# Power.net
KiCad netlist of a schematic drawn in Altium Designer
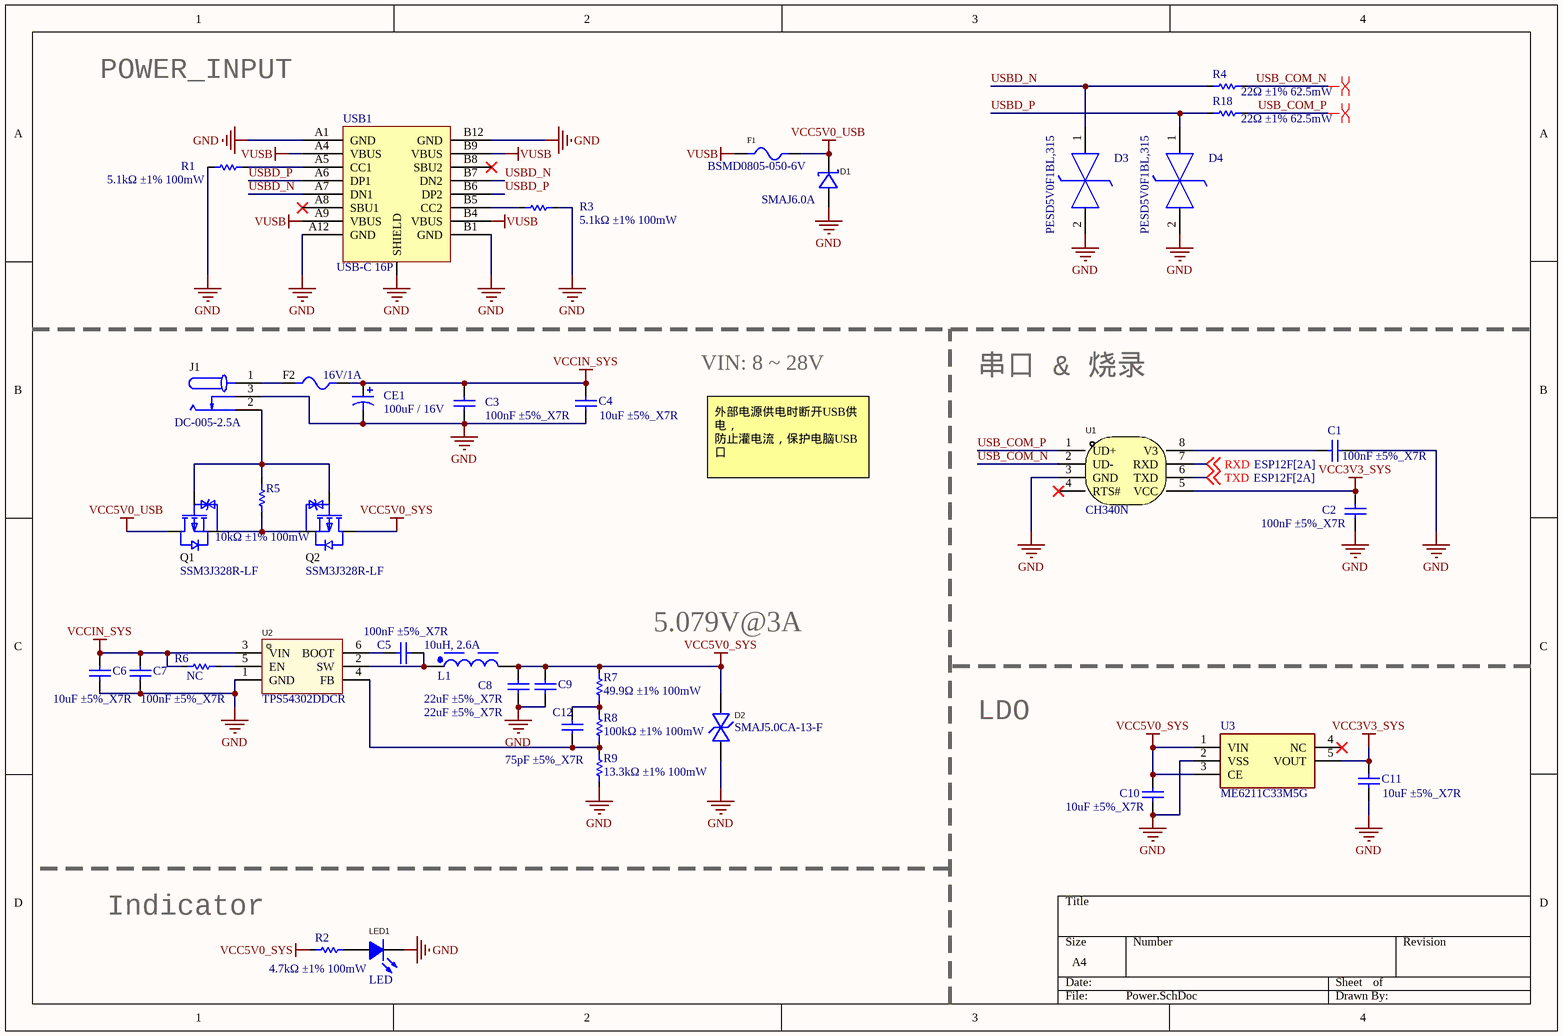
[diagram p0: Power.SchDoc]

(export (version "E")
  (design (tool "Eeschema 10.0.6"))
  (components
    (comp (ref "C1")
      (value "100nF ±5%_X7R")
      (footprint "C0603")
      (description "Capacitor")
      (fields (field (name "PUBLISHER") "Altium Limited"))
      (libsource (lib "Component") (part "Cap"))
    )
    (comp (ref "C2")
      (value "100nF ±5%_X7R")
      (footprint "C0603")
      (description "Capacitor")
      (fields (field (name "PUBLISHER") "Altium Limited"))
      (libsource (lib "Component") (part "Cap"))
    )
    (comp (ref "C3")
      (value "100nF ±5%_X7R")
      (footprint "C0603")
      (description "Capacitor")
      (fields (field (name "PUBLISHER") "Altium Limited"))
      (libsource (lib "Component") (part "Cap"))
    )
    (comp (ref "C4")
      (value "10uF ±5%_X7R")
      (footprint "C0603")
      (description "Capacitor")
      (fields (field (name "PUBLISHER") "Altium Limited"))
      (libsource (lib "Component") (part "Cap"))
    )
    (comp (ref "C5")
      (value "100nF ±5%_X7R")
      (footprint "C0402")
      (description "Capacitor")
      (fields (field (name "PUBLISHER") "Altium Limited"))
      (libsource (lib "Component") (part "Cap"))
    )
    (comp (ref "C6")
      (value "10uF ±5%_X7R")
      (footprint "C0603")
      (description "Capacitor")
      (fields (field (name "PUBLISHER") "Altium Limited"))
      (libsource (lib "Component") (part "Cap"))
    )
    (comp (ref "C7")
      (value "100nF ±5%_X7R")
      (footprint "C0603")
      (description "Capacitor")
      (fields (field (name "PUBLISHER") "Altium Limited"))
      (libsource (lib "Component") (part "Cap"))
    )
    (comp (ref "C8")
      (value "22uF ±5%_X7R")
      (footprint "C0603")
      (description "Capacitor")
      (fields (field (name "PUBLISHER") "Altium Limited"))
      (libsource (lib "Component") (part "Cap"))
    )
    (comp (ref "C9")
      (value "22uF ±5%_X7R")
      (footprint "C0603")
      (description "Capacitor")
      (fields (field (name "PUBLISHER") "Altium Limited"))
      (libsource (lib "Component") (part "Cap"))
    )
    (comp (ref "C10")
      (value "10uF ±5%_X7R")
      (footprint "C0603")
      (description "Capacitor")
      (fields (field (name "PUBLISHER") "Altium Limited"))
      (libsource (lib "Component") (part "Cap"))
    )
    (comp (ref "C11")
      (value "10uF ±5%_X7R")
      (footprint "C0603")
      (description "Capacitor")
      (fields (field (name "PUBLISHER") "Altium Limited"))
      (libsource (lib "Component") (part "Cap"))
    )
    (comp (ref "C12")
      (value "75pF ±5%_X7R")
      (footprint "C0402")
      (description "Capacitor")
      (fields (field (name "PUBLISHER") "Altium Limited"))
      (libsource (lib "Component") (part "Cap"))
    )
    (comp (ref "CE1")
      (value "100uF / 16V")
      (footprint "CAP-SMD")
      (description "Polarized Capacitor (Axial)")
      (fields (field (name "PUBLISHER") "Altium Limited"))
      (libsource (lib "Component") (part "Cap Pol"))
    )
    (comp (ref "D1")
      (value "SMAJ6.0A")
      (footprint "SMA_L4.4-W2.6-LS5.0-RD")
      (fields (field (name "MANUFACTURER") "BORN(伯恩半导体)"))
      (libsource (lib "Component") (part "SMAJ6.0A_C152112"))
    )
    (comp (ref "D2")
      (value "SMAJ5.0CA-13-F")
      (footprint "SMA_L4.4-W2.6-LS5.0-BI")
      (fields (field (name "MANUFACTURER") "DIODES(美台)"))
      (libsource (lib "Component") (part "SMAJ5.0CA"))
    )
    (comp (ref "D3")
      (value "PESD5V0F1BL,315")
      (footprint "SamacSys:PESD5V0S1BL315")
      (description "Diode ESD (Bi-directional)")
      (fields (field (name "MOUSER PART NUMBER") "771-PESD5V0F1BL315"))
      (libsource (lib "*") (part "PESD5V0F1BL,315"))
    )
    (comp (ref "D4")
      (value "PESD5V0F1BL,315")
      (footprint "SamacSys:PESD5V0S1BL315")
      (description "Diode ESD (Bi-directional)")
      (fields (field (name "MOUSER PART NUMBER") "771-PESD5V0F1BL315"))
      (libsource (lib "*") (part "PESD5V0F1BL,315"))
    )
    (comp (ref "F1")
      (value "BSMD0805-050-6V")
      (footprint "F0805")
      (fields (field (name "MANUFACTURER") "BHFUSE(佰宏)"))
      (libsource (lib "Component_Footprints") (part "BSMD0805-050-6V"))
    )
    (comp (ref "F2")
      (value "16V/1A")
      (footprint "F1206")
      (fields (field (name "MANUFACTURER") "BHFUSE(佰宏)") (field (name "MANUFACTURER PART") "BSMD0805-050-6V"))
      (libsource (lib "Component") (part "FUSE"))
    )
    (comp (ref "J1")
      (value "DC-005-2.5A")
      (footprint "CONN-TH_DC-005-2.5A-2.0")
      (fields
        (field (name "MANUFACTURER") "XKB Connectivity(中国星坤)")
        (field (name "MANUFACTURER PART") "DC-005-2.5A-2.5")
      )
      (libsource (lib "Connectivity_Plugs") (part "DC-005"))
    )
    (comp (ref "L1")
      (value "10uH, 2.6A")
      (footprint "WE-PD_7345P")
      (description "WE-PD SMT Power Inductor, size 7345P, 10uH, 2.6A, 45mOhm")
      (fields
        (field (name "MANUFACTURER PART NUMBER") "7447773100")
        (field (name "MANUFACTURER") "Wurth Elektronik")
      )
      (libsource (lib "WE-PD (rev22g)") (part "7447773100"))
    )
    (comp (ref "LED1")
      (value "LED")
      (footprint "LED0603-RD")
      (fields
        (field (name "MANUFACTURER") "EVERLIGHT(亿光)")
        (field (name "MANUFACTURER PART") "17-21SURC/S530-A2/TR8")
      )
      (libsource (lib "Component") (part "LED"))
    )
    (comp (ref "Q1")
      (value "SSM3J328R-LF")
      (footprint "SOT-23-3_L2.9-W1.4-P1.91-LS2.6-BR")
      (fields (field (name "MANUFACTURER") "VBsemi(微碧)") (field (name "MANUFACTURER PART") "SSM3J328R-VB"))
      (libsource (lib "Component") (part "MOSFET"))
    )
    (comp (ref "Q2")
      (value "SSM3J328R-LF")
      (footprint "SOT-23-3_L2.9-W1.4-P1.91-LS2.6-BR")
      (fields (field (name "MANUFACTURER") "VBsemi(微碧)") (field (name "MANUFACTURER PART") "SSM3J328R-VB"))
      (libsource (lib "Component") (part "MOSFET"))
    )
    (comp (ref "R1")
      (value "5.1kΩ ±1% 100mW")
      (footprint "R0402")
      (description "Resistor")
      (fields (field (name "PUBLISHER") "Altium Limited"))
      (libsource (lib "Component_Footprints") (part "Res"))
    )
    (comp (ref "R2")
      (value "4.7kΩ ±1% 100mW")
      (footprint "R0603")
      (description "Resistor")
      (fields (field (name "PUBLISHER") "Altium Limited"))
      (libsource (lib "Component_Footprints") (part "Res"))
    )
    (comp (ref "R3")
      (value "5.1kΩ ±1% 100mW")
      (footprint "R0402")
      (description "Resistor")
      (fields (field (name "PUBLISHER") "Altium Limited"))
      (libsource (lib "Component_Footprints") (part "Res"))
    )
    (comp (ref "R4")
      (value "22Ω ±1% 62.5mW")
      (footprint "R0402")
      (description "Resistor")
      (fields (field (name "PUBLISHER") "Altium Limited"))
      (libsource (lib "Component") (part "Res"))
    )
    (comp (ref "R5")
      (value "10kΩ ±1% 100mW")
      (footprint "R0603")
      (description "Resistor")
      (fields (field (name "PUBLISHER") "Altium Limited"))
      (libsource (lib "Component") (part "Res"))
    )
    (comp (ref "R6")
      (value "NC")
      (footprint "R0402")
      (description "Resistor")
      (fields (field (name "PUBLISHER") "Altium Limited"))
      (libsource (lib "Component") (part "Res"))
    )
    (comp (ref "R7")
      (value "49.9Ω ±1% 100mW")
      (footprint "R0402")
      (description "Resistor")
      (fields (field (name "PUBLISHER") "Altium Limited"))
      (libsource (lib "Component") (part "Res"))
    )
    (comp (ref "R8")
      (value "100kΩ ±1% 100mW")
      (footprint "R0402")
      (description "Resistor")
      (fields (field (name "PUBLISHER") "Altium Limited"))
      (libsource (lib "Component") (part "Res"))
    )
    (comp (ref "R9")
      (value "13.3kΩ ±1% 100mW")
      (footprint "R0402")
      (description "Resistor")
      (fields (field (name "PUBLISHER") "Altium Limited"))
      (libsource (lib "Component") (part "Res"))
    )
    (comp (ref "R18")
      (value "22Ω ±1% 62.5mW")
      (footprint "R0402")
      (description "Resistor")
      (fields (field (name "PUBLISHER") "Altium Limited"))
      (libsource (lib "Component") (part "Res"))
    )
    (comp (ref "U1")
      (value "CH340N")
      (footprint "SOP-8_L4.9-W3.9-P1.27-LS6.0-BL")
      (fields (field (name "MANUFACTURER") "WCH(南京沁恒)"))
      (libsource (lib "IC") (part "CH340N"))
    )
    (comp (ref "U2")
      (value "TPS54302DDCR")
      (footprint "SOT-23-6_L2.9-W1.6-P0.95-LS2.8-BL")
      (fields (field (name "MANUFACTURER") "TI(德州仪器)"))
      (libsource (lib "IC") (part "TPS54302DDCR"))
    )
    (comp (ref "U3")
      (value "ME6211C33M5G")
      (footprint "SamacSys:SOT95P282X145-5N")
      (description "Integrated Circuit")
      (libsource (lib "*") (part "ME6211C33M5G"))
    )
    (comp (ref "USB1") (value "USB-C 16P") (footprint "USB-C-16P") (libsource (lib "USB") (part "USB-C 16P")))
  )
  (nets
    (net (code "1") (name "/USBD_N") (class "Default")
      (node (ref "D3") (pin "1") (pinfunction "K1_1") (pintype "passive"))
      (node (ref "R4") (pin "1") (pinfunction "1_1") (pintype "passive"))
      (node (ref "USB1") (pin "A7") (pinfunction "DN1_A7") (pintype "passive"))
      (node (ref "USB1") (pin "B7") (pinfunction "DN2_B7") (pintype "passive"))
    )
    (net (code "2") (name "/USBD_P") (class "Default")
      (node (ref "D4") (pin "1") (pinfunction "K1_1") (pintype "passive"))
      (node (ref "R18") (pin "1") (pinfunction "1_1") (pintype "passive"))
      (node (ref "USB1") (pin "A6") (pinfunction "DP1_A6") (pintype "passive"))
      (node (ref "USB1") (pin "B6") (pinfunction "DP2_B6") (pintype "passive"))
    )
    (net (code "3") (name "/USB_COM_N") (class "Default")
      (node (ref "R4") (pin "2") (pinfunction "2_2") (pintype "passive"))
      (node (ref "U1") (pin "2") (pinfunction "UD-_2") (pintype "passive"))
    )
    (net (code "4") (name "/USB_COM_P") (class "Default")
      (node (ref "R18") (pin "2") (pinfunction "2_2") (pintype "passive"))
      (node (ref "U1") (pin "1") (pinfunction "UD+_1") (pintype "passive"))
    )
    (net (code "5") (name "GND") (class "Default")
      (node (ref "C1") (pin "1") (pinfunction "1_1") (pintype "passive"))
      (node (ref "C10") (pin "1") (pinfunction "1_1") (pintype "passive"))
      (node (ref "C11") (pin "1") (pinfunction "1_1") (pintype "passive"))
      (node (ref "C2") (pin "1") (pinfunction "1_1") (pintype "passive"))
      (node (ref "C3") (pin "1") (pinfunction "1_1") (pintype "passive"))
      (node (ref "C4") (pin "1") (pinfunction "1_1") (pintype "passive"))
      (node (ref "C6") (pin "1") (pinfunction "1_1") (pintype "passive"))
      (node (ref "C7") (pin "1") (pinfunction "1_1") (pintype "passive"))
      (node (ref "C8") (pin "1") (pinfunction "1_1") (pintype "passive"))
      (node (ref "C9") (pin "1") (pinfunction "1_1") (pintype "passive"))
      (node (ref "CE1") (pin "2") (pinfunction "2_2") (pintype "passive"))
      (node (ref "D1") (pin "2") (pinfunction "A_2") (pintype "passive"))
      (node (ref "D2") (pin "1") (pinfunction "1_1") (pintype "passive"))
      (node (ref "D3") (pin "2") (pinfunction "K2_2") (pintype "passive"))
      (node (ref "D4") (pin "2") (pinfunction "K2_2") (pintype "passive"))
      (node (ref "J1") (pin "3") (pinfunction "3_3") (pintype "passive"))
      (node (ref "LED1") (pin "2") (pinfunction "K_2") (pintype "passive"))
      (node (ref "R1") (pin "1") (pinfunction "1_1") (pintype "passive"))
      (node (ref "R3") (pin "2") (pinfunction "2_2") (pintype "passive"))
      (node (ref "R9") (pin "1") (pinfunction "1_1") (pintype "passive"))
      (node (ref "U1") (pin "3") (pinfunction "GND_3") (pintype "passive"))
      (node (ref "U2") (pin "1") (pinfunction "GND_1") (pintype "passive"))
      (node (ref "U3") (pin "2") (pinfunction "VSS_2") (pintype "passive"))
      (node (ref "USB1") (pin "0") (pinfunction "SHIELD_0") (pintype "passive"))
      (node (ref "USB1") (pin "A1") (pinfunction "GND_A1") (pintype "passive"))
      (node (ref "USB1") (pin "A12") (pinfunction "GND_A12") (pintype "passive"))
      (node (ref "USB1") (pin "B1") (pinfunction "GND_B1") (pintype "passive"))
      (node (ref "USB1") (pin "B12") (pinfunction "GND_B12") (pintype "passive"))
    )
    (net (code "6") (name "Net-(C12-Pad2)") (class "Default")
      (node (ref "C12") (pin "2") (pinfunction "2_2") (pintype "passive"))
      (node (ref "R7") (pin "1") (pinfunction "1_1") (pintype "passive"))
      (node (ref "R8") (pin "2") (pinfunction "2_2") (pintype "passive"))
    )
    (net (code "7") (name "Net-(F2-Pad1)") (class "Default")
      (node (ref "F2") (pin "1") (pinfunction "1_1") (pintype "passive"))
      (node (ref "J1") (pin "1") (pinfunction "1_1") (pintype "passive"))
    )
    (net (code "8") (name "Net-(LED1-A)") (class "Default")
      (node (ref "LED1") (pin "1") (pinfunction "A_1") (pintype "passive"))
      (node (ref "R2") (pin "2") (pinfunction "2_2") (pintype "passive"))
    )
    (net (code "9") (name "Net-(Q1-G)") (class "Default")
      (node (ref "J1") (pin "2") (pinfunction "2_2") (pintype "passive"))
      (node (ref "Q1") (pin "1") (pinfunction "G_1") (pintype "passive"))
      (node (ref "Q2") (pin "1") (pinfunction "G_1") (pintype "passive"))
      (node (ref "R5") (pin "1") (pinfunction "1_1") (pintype "passive"))
    )
    (net (code "10") (name "Net-(Q1-S)") (class "Default")
      (node (ref "Q1") (pin "2") (pinfunction "S_2") (pintype "passive"))
      (node (ref "Q2") (pin "2") (pinfunction "S_2") (pintype "passive"))
      (node (ref "R5") (pin "2") (pinfunction "2_2") (pintype "passive"))
    )
    (net (code "11") (name "Net-(U1-V3)") (class "Default")
      (node (ref "C1") (pin "2") (pinfunction "2_2") (pintype "passive"))
      (node (ref "U1") (pin "8") (pinfunction "V3_8") (pintype "passive"))
    )
    (net (code "12") (name "Net-(U2-BOOT)") (class "Default")
      (node (ref "C5") (pin "2") (pinfunction "2_2") (pintype "passive"))
      (node (ref "U2") (pin "6") (pinfunction "BOOT_6") (pintype "passive"))
    )
    (net (code "13") (name "Net-(U2-EN)") (class "Default")
      (node (ref "R6") (pin "1") (pinfunction "1_1") (pintype "passive"))
      (node (ref "U2") (pin "5") (pinfunction "EN_5") (pintype "passive"))
    )
    (net (code "14") (name "Net-(U2-FB)") (class "Default")
      (node (ref "C12") (pin "1") (pinfunction "1_1") (pintype "passive"))
      (node (ref "R8") (pin "1") (pinfunction "1_1") (pintype "passive"))
      (node (ref "R9") (pin "2") (pinfunction "2_2") (pintype "passive"))
      (node (ref "U2") (pin "4") (pinfunction "FB_4") (pintype "passive"))
    )
    (net (code "15") (name "Net-(U2-SW)") (class "Default")
      (node (ref "C5") (pin "1") (pinfunction "1_1") (pintype "passive"))
      (node (ref "L1") (pin "1") (pinfunction "1_1") (pintype "passive"))
      (node (ref "U2") (pin "2") (pinfunction "SW_2") (pintype "passive"))
    )
    (net (code "16") (name "Net-(USB1-CC1)") (class "Default")
      (node (ref "R1") (pin "2") (pinfunction "2_2") (pintype "passive"))
      (node (ref "USB1") (pin "A5") (pinfunction "CC1_A5") (pintype "passive"))
    )
    (net (code "17") (name "Net-(USB1-CC2)") (class "Default")
      (node (ref "R3") (pin "1") (pinfunction "1_1") (pintype "passive"))
      (node (ref "USB1") (pin "B5") (pinfunction "CC2_B5") (pintype "passive"))
    )
    (net (code "18") (name "RXD") (class "Default")
      (node (ref "U1") (pin "7") (pinfunction "RXD_7") (pintype "passive"))
    )
    (net (code "19") (name "TXD") (class "Default")
      (node (ref "U1") (pin "6") (pinfunction "TXD_6") (pintype "passive"))
    )
    (net (code "20") (name "VCC3V3_SYS") (class "Default")
      (node (ref "C11") (pin "2") (pinfunction "2_2") (pintype "passive"))
      (node (ref "C2") (pin "2") (pinfunction "2_2") (pintype "passive"))
      (node (ref "U1") (pin "5") (pinfunction "VCC_5") (pintype "passive"))
      (node (ref "U3") (pin "5") (pinfunction "VOUT_5") (pintype "passive"))
    )
    (net (code "21") (name "VCC5V0_SYS") (class "Default")
      (node (ref "C10") (pin "2") (pinfunction "2_2") (pintype "passive"))
      (node (ref "C8") (pin "2") (pinfunction "2_2") (pintype "passive"))
      (node (ref "C9") (pin "2") (pinfunction "2_2") (pintype "passive"))
      (node (ref "D2") (pin "2") (pinfunction "2_2") (pintype "passive"))
      (node (ref "L1") (pin "2") (pinfunction "2_2") (pintype "passive"))
      (node (ref "Q2") (pin "3") (pinfunction "D_3") (pintype "passive"))
      (node (ref "R2") (pin "1") (pinfunction "1_1") (pintype "passive"))
      (node (ref "R7") (pin "2") (pinfunction "2_2") (pintype "passive"))
      (node (ref "U3") (pin "1") (pinfunction "VIN_1") (pintype "passive"))
      (node (ref "U3") (pin "3") (pinfunction "CE_3") (pintype "passive"))
    )
    (net (code "22") (name "VCC5V0_USB") (class "Default")
      (node (ref "D1") (pin "1") (pinfunction "K_1") (pintype "passive"))
      (node (ref "F1") (pin "2") (pinfunction "2_2") (pintype "passive"))
      (node (ref "Q1") (pin "3") (pinfunction "D_3") (pintype "passive"))
    )
    (net (code "23") (name "VCCIN_SYS") (class "Default")
      (node (ref "C3") (pin "2") (pinfunction "2_2") (pintype "passive"))
      (node (ref "C4") (pin "2") (pinfunction "2_2") (pintype "passive"))
      (node (ref "C6") (pin "2") (pinfunction "2_2") (pintype "passive"))
      (node (ref "C7") (pin "2") (pinfunction "2_2") (pintype "passive"))
      (node (ref "CE1") (pin "1") (pinfunction "1_1") (pintype "passive"))
      (node (ref "F2") (pin "2") (pinfunction "2_2") (pintype "passive"))
      (node (ref "R6") (pin "2") (pinfunction "2_2") (pintype "passive"))
      (node (ref "U2") (pin "3") (pinfunction "VIN_3") (pintype "passive"))
    )
    (net (code "24") (name "VUSB") (class "Default")
      (node (ref "F1") (pin "1") (pinfunction "1_1") (pintype "passive"))
      (node (ref "USB1") (pin "A4") (pinfunction "VBUS_A4") (pintype "passive"))
      (node (ref "USB1") (pin "A9") (pinfunction "VBUS_A9") (pintype "passive"))
      (node (ref "USB1") (pin "B4") (pinfunction "VBUS_B4") (pintype "passive"))
      (node (ref "USB1") (pin "B9") (pinfunction "VBUS_B9") (pintype "passive"))
    )
    (net (code "25") (name "unconnected-(U1-RTS#-Pad4)") (class "Default")
      (node (ref "U1") (pin "4") (pinfunction "RTS#_4") (pintype "passive+no_connect"))
    )
    (net (code "26") (name "unconnected-(U3-NC-Pad4)") (class "Default")
      (node (ref "U3") (pin "4") (pinfunction "NC_4") (pintype "passive+no_connect"))
    )
    (net (code "27") (name "unconnected-(USB1-SBU1-PadA8)") (class "Default")
      (node (ref "USB1") (pin "A8") (pinfunction "SBU1_A8") (pintype "passive+no_connect"))
    )
    (net (code "28") (name "unconnected-(USB1-SBU2-PadB8)") (class "Default")
      (node (ref "USB1") (pin "B8") (pinfunction "SBU2_B8") (pintype "passive+no_connect"))
    )
  )
)
